# QSFP.net
KiCad netlist of a schematic drawn in Altium Designer
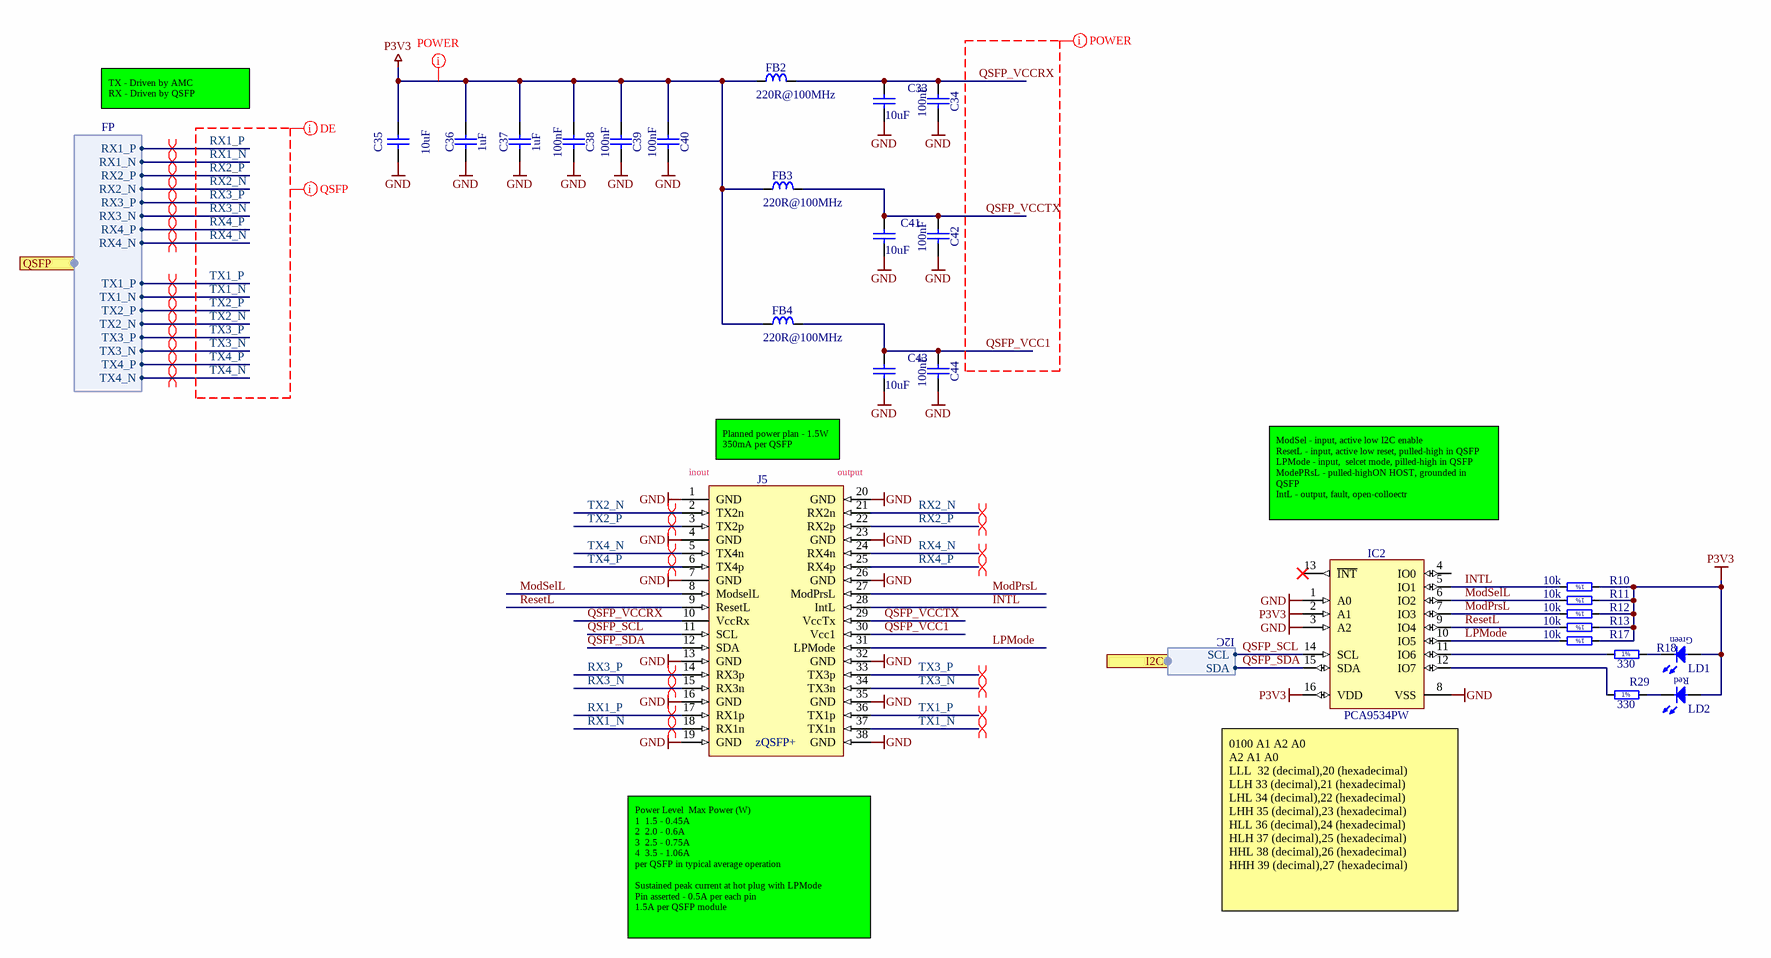
[diagram p0: QSFP.SchDoc]

(export (version "E")
  (design (tool "Eeschema 10.0.6"))
  (components
    (comp (ref "C33")
      (value "10uF")
      (footprint "CAPC2012X135N")
      (description "Non-polarised capacitor")
      (fields
        (field (name "PART NUMBER") "CC0805_10UF_10V_10%_X7R")
        (field (name "VOLTAGE") "10V")
        (field (name "AUTHOR") "CERN DEM JLC")
      )
      (libsource (lib "Capacitors") (part "Capacitor - non polarized"))
    )
    (comp (ref "C34")
      (value "100nF")
      (footprint "CAPC0603X33N")
      (description "Non-polarised capacitor")
      (fields
        (field (name "PART NUMBER") "CC0201_100NF_6.3V_10%_X5R")
        (field (name "VOLTAGE") "6.3V")
        (field (name "AUTHOR") "CERN DEM JLC")
      )
      (libsource (lib "Capacitors") (part "Capacitor - non polarized"))
    )
    (comp (ref "C35")
      (value "10uF")
      (footprint "CAPC2012X135N")
      (description "Non-polarised capacitor")
      (fields
        (field (name "PART NUMBER") "CC0805_10UF_10V_10%_X7R")
        (field (name "VOLTAGE") "10V")
        (field (name "AUTHOR") "CERN DEM JLC")
      )
      (libsource (lib "Capacitors") (part "Capacitor - non polarized"))
    )
    (comp (ref "C36")
      (value "1uF")
      (footprint "CAPC1608X87N")
      (description "Non-polarised capacitor")
      (fields
        (field (name "PART NUMBER") "CC0603_1UF_25V_10%_X7R")
        (field (name "VOLTAGE") "25V")
        (field (name "AUTHOR") "CERN DEM JLC")
      )
      (libsource (lib "Capacitors") (part "Capacitor - non polarized"))
    )
    (comp (ref "C37")
      (value "1uF")
      (footprint "CAPC1608X87N")
      (description "Non-polarised capacitor")
      (fields
        (field (name "PART NUMBER") "CC0603_1UF_25V_10%_X7R")
        (field (name "VOLTAGE") "25V")
        (field (name "AUTHOR") "CERN DEM JLC")
      )
      (libsource (lib "Capacitors") (part "Capacitor - non polarized"))
    )
    (comp (ref "C38")
      (value "100nF")
      (footprint "CAPC0603X33N")
      (description "Non-polarised capacitor")
      (fields
        (field (name "PART NUMBER") "CC0201_100NF_6.3V_10%_X5R")
        (field (name "VOLTAGE") "6.3V")
        (field (name "AUTHOR") "CERN DEM JLC")
      )
      (libsource (lib "Capacitors") (part "Capacitor - non polarized"))
    )
    (comp (ref "C39")
      (value "100nF")
      (footprint "CAPC0603X33N")
      (description "Non-polarised capacitor")
      (fields
        (field (name "PART NUMBER") "CC0201_100NF_6.3V_10%_X5R")
        (field (name "VOLTAGE") "6.3V")
        (field (name "AUTHOR") "CERN DEM JLC")
      )
      (libsource (lib "Capacitors") (part "Capacitor - non polarized"))
    )
    (comp (ref "C40")
      (value "100nF")
      (footprint "CAPC0603X33N")
      (description "Non-polarised capacitor")
      (fields
        (field (name "PART NUMBER") "CC0201_100NF_6.3V_10%_X5R")
        (field (name "VOLTAGE") "6.3V")
        (field (name "AUTHOR") "CERN DEM JLC")
      )
      (libsource (lib "Capacitors") (part "Capacitor - non polarized"))
    )
    (comp (ref "C41")
      (value "10uF")
      (footprint "CAPC2012X135N")
      (description "Non-polarised capacitor")
      (fields
        (field (name "PART NUMBER") "CC0805_10UF_10V_10%_X7R")
        (field (name "VOLTAGE") "10V")
        (field (name "AUTHOR") "CERN DEM JLC")
      )
      (libsource (lib "Capacitors") (part "Capacitor - non polarized"))
    )
    (comp (ref "C42")
      (value "100nF")
      (footprint "CAPC0603X33N")
      (description "Non-polarised capacitor")
      (fields
        (field (name "PART NUMBER") "CC0201_100NF_6.3V_10%_X5R")
        (field (name "VOLTAGE") "6.3V")
        (field (name "AUTHOR") "CERN DEM JLC")
      )
      (libsource (lib "Capacitors") (part "Capacitor - non polarized"))
    )
    (comp (ref "C43")
      (value "10uF")
      (footprint "CAPC2012X135N")
      (description "Non-polarised capacitor")
      (fields
        (field (name "PART NUMBER") "CC0805_10UF_10V_10%_X7R")
        (field (name "VOLTAGE") "10V")
        (field (name "AUTHOR") "CERN DEM JLC")
      )
      (libsource (lib "Capacitors") (part "Capacitor - non polarized"))
    )
    (comp (ref "C44")
      (value "100nF")
      (footprint "CAPC0603X33N")
      (description "Non-polarised capacitor")
      (fields
        (field (name "PART NUMBER") "CC0201_100NF_6.3V_10%_X5R")
        (field (name "VOLTAGE") "6.3V")
        (field (name "AUTHOR") "CERN DEM JLC")
      )
      (libsource (lib "Capacitors") (part "Capacitor - non polarized"))
    )
    (comp (ref "FB2")
      (value "220R@100MHz")
      (footprint "INDC2012X105N")
      (description "Inductor")
      (fields
        (field (name "PART NUMBER") "IND0805_MURATA_BLM21PG221SN1D")
        (field (name "POWER") "2A")
        (field (name "AUTHOR") "CERN DEM JLC")
      )
      (libsource (lib "Inductors & Transformers") (part "Inductor"))
    )
    (comp (ref "FB3")
      (value "220R@100MHz")
      (footprint "INDC2012X105N")
      (description "Inductor")
      (fields
        (field (name "PART NUMBER") "IND0805_MURATA_BLM21PG221SN1D")
        (field (name "POWER") "2A")
        (field (name "AUTHOR") "CERN DEM JLC")
      )
      (libsource (lib "Inductors & Transformers") (part "Inductor"))
    )
    (comp (ref "FB4")
      (value "220R@100MHz")
      (footprint "INDC2012X105N")
      (description "Inductor")
      (fields
        (field (name "PART NUMBER") "IND0805_MURATA_BLM21PG221SN1D")
        (field (name "POWER") "2A")
        (field (name "AUTHOR") "CERN DEM JLC")
      )
      (libsource (lib "Inductors & Transformers") (part "Inductor"))
    )
    (comp (ref "IC2")
      (value "PCA9534PW")
      (footprint "SOP65P640X110-16N")
      (description "8-Bit I2C-Bus and SMBus Low Power I/O Port with Interrupt")
      (fields (field (name "MANUFACTURER") "ANALOG DEVICES") (field (name "AUTHOR") "CERN DEM JLC"))
      (libsource (lib "ICs And Semiconductors") (part "PCA9534PW"))
    )
    (comp (ref "J5")
      (value "zQSFP+")
      (footprint "TYCO_1551920-2")
      (description "38Position QSFP Connector  (Quad Small Form-factor Pluggable)")
      (fields
        (field (name "PART NUMBER") "TYCO_1551920-2")
        (field (name "MANUFACTURER") "TYCO ELECTRONICS")
        (field (name "AUTHOR") "CERN DEM JLC")
      )
      (libsource (lib "Connectors") (part "QSFP+x1"))
    )
    (comp (ref "LD1")
      (value "LED_AVAGO_HSME-C120")
      (footprint "LED_AVAGO_HSME-C120")
      (description "LED Green 1C 2A")
      (fields
        (field (name "MANUFACTURER") "AVAGO TECHNOLOGIES")
        (field (name "MANUFACTURER PART NUMBER") "HSME-C120")
        (field (name "AUTHOR") "CERN DEM JMW")
      )
      (libsource (lib "ICs And Semiconductors") (part "LED Green 1C 2A"))
    )
    (comp (ref "LD2")
      (value "Red")
      (footprint "LED_AVAGO_HSME-C120rev")
      (description "LED Red Avago C120")
      (fields
        (field (name "PART NUMBER") "LED_AVAGO_HSMC-C120")
        (field (name "MANUFACTURER") "AVAGO TECHNOLOGIES")
        (field (name "AUTHOR") "CERN DEM JMW")
      )
      (libsource (lib "LIBRARY_SCH") (part "LED_SMD_90deg_mini_R"))
    )
    (comp (ref "R10")
      (value "10k")
      (footprint "RESC1005X40N")
      (description "Resistor - 1%")
      (fields
        (field (name "PART NUMBER") "R0402_10K_1%_0.0625W_100PPM")
        (field (name "POWER") "0.0625W")
        (field (name "AUTHOR") "CERN DEM JLC")
      )
      (libsource (lib "Resistors") (part "Resistor - 1%"))
    )
    (comp (ref "R11")
      (value "10k")
      (footprint "RESC1005X40N")
      (description "Resistor - 1%")
      (fields
        (field (name "PART NUMBER") "R0402_10K_1%_0.0625W_100PPM")
        (field (name "POWER") "0.0625W")
        (field (name "AUTHOR") "CERN DEM JLC")
      )
      (libsource (lib "Resistors") (part "Resistor - 1%"))
    )
    (comp (ref "R12")
      (value "10k")
      (footprint "RESC1005X40N")
      (description "Resistor - 1%")
      (fields
        (field (name "PART NUMBER") "R0402_10K_1%_0.0625W_100PPM")
        (field (name "POWER") "0.0625W")
        (field (name "AUTHOR") "CERN DEM JLC")
      )
      (libsource (lib "Resistors") (part "Resistor - 1%"))
    )
    (comp (ref "R13")
      (value "10k")
      (footprint "RESC1005X40N")
      (description "Resistor - 1%")
      (fields
        (field (name "PART NUMBER") "R0402_10K_1%_0.0625W_100PPM")
        (field (name "POWER") "0.0625W")
        (field (name "AUTHOR") "CERN DEM JLC")
      )
      (libsource (lib "Resistors") (part "Resistor - 1%"))
    )
    (comp (ref "R17")
      (value "10k")
      (footprint "RESC1005X40N")
      (description "Resistor - 1%")
      (fields
        (field (name "PART NUMBER") "R0402_10K_1%_0.0625W_100PPM")
        (field (name "POWER") "0.0625W")
        (field (name "AUTHOR") "CERN DEM JLC")
      )
      (libsource (lib "Resistors") (part "Resistor - 1%"))
    )
    (comp (ref "R18")
      (value "330")
      (footprint "RESC1608X55N")
      (description "Resistor - 1%")
      (fields
        (field (name "PART NUMBER") "R0603_330R_1%_0.1W_100PPM")
        (field (name "POWER") "0.1W")
        (field (name "AUTHOR") "CERN DEM JLC")
      )
      (libsource (lib "Resistors") (part "Resistor - 1%"))
    )
    (comp (ref "R29")
      (value "330")
      (footprint "RESC1608X55N")
      (description "Resistor - 1%")
      (fields
        (field (name "PART NUMBER") "R0603_330R_1%_0.1W_100PPM")
        (field (name "POWER") "0.1W")
        (field (name "AUTHOR") "CERN DEM JLC")
      )
      (libsource (lib "Resistors") (part "Resistor - 1%"))
    )
  )
  (nets
    (net (code "3") (name "/INTL") (class "Default")
      (node (ref "IC2") (pin "5") (pinfunction "IO1_5") (pintype "bidirectional"))
      (node (ref "J5") (pin "28") (pinfunction "IntL_28") (pintype "input"))
      (node (ref "R10") (pin "2") (pinfunction "2_2") (pintype "passive"))
    )
    (net (code "4") (name "/LPMode") (class "Default")
      (node (ref "IC2") (pin "10") (pinfunction "IO5_10") (pintype "bidirectional"))
      (node (ref "J5") (pin "31") (pinfunction "LPMode_31") (pintype "input"))
      (node (ref "R17") (pin "2") (pinfunction "2_2") (pintype "passive"))
    )
    (net (code "5") (name "/ModPrsL") (class "Default")
      (node (ref "IC2") (pin "7") (pinfunction "IO3_7") (pintype "bidirectional"))
      (node (ref "J5") (pin "27") (pinfunction "ModPrsL_27") (pintype "input"))
      (node (ref "R12") (pin "2") (pinfunction "2_2") (pintype "passive"))
    )
    (net (code "6") (name "/ModSelL") (class "Default")
      (node (ref "IC2") (pin "6") (pinfunction "IO2_6") (pintype "bidirectional"))
      (node (ref "J5") (pin "8") (pinfunction "ModselL_8") (pintype "input"))
      (node (ref "R11") (pin "2") (pinfunction "2_2") (pintype "passive"))
    )
    (net (code "7") (name "/QSFP_SCL") (class "Default")
      (node (ref "IC2") (pin "14") (pinfunction "SCL_14") (pintype "input"))
      (node (ref "J5") (pin "11") (pinfunction "SCL_11") (pintype "input"))
    )
    (net (code "8") (name "/QSFP_SDA") (class "Default")
      (node (ref "IC2") (pin "15") (pinfunction "SDA_15") (pintype "bidirectional"))
      (node (ref "J5") (pin "12") (pinfunction "SDA_12") (pintype "input"))
    )
    (net (code "9") (name "/QSFP_VCC1") (class "Default")
      (node (ref "C43") (pin "1") (pinfunction "1_1") (pintype "passive"))
      (node (ref "C44") (pin "1") (pinfunction "1_1") (pintype "passive"))
      (node (ref "FB4") (pin "2") (pinfunction "2_2") (pintype "passive"))
      (node (ref "J5") (pin "30") (pinfunction "Vcc1_30") (pintype "input"))
    )
    (net (code "10") (name "/QSFP_VCCRX") (class "Default")
      (node (ref "C33") (pin "1") (pinfunction "1_1") (pintype "passive"))
      (node (ref "C34") (pin "1") (pinfunction "1_1") (pintype "passive"))
      (node (ref "FB2") (pin "2") (pinfunction "2_2") (pintype "passive"))
      (node (ref "J5") (pin "10") (pinfunction "VccRx_10") (pintype "power_in"))
    )
    (net (code "11") (name "/QSFP_VCCTX") (class "Default")
      (node (ref "C41") (pin "1") (pinfunction "1_1") (pintype "passive"))
      (node (ref "C42") (pin "1") (pinfunction "1_1") (pintype "passive"))
      (node (ref "FB3") (pin "2") (pinfunction "2_2") (pintype "passive"))
      (node (ref "J5") (pin "29") (pinfunction "VccTx_29") (pintype "input"))
    )
    (net (code "12") (name "/RX1_N") (class "Default")
      (node (ref "J5") (pin "18") (pinfunction "RX1n_18") (pintype "input"))
    )
    (net (code "13") (name "/RX1_P") (class "Default")
      (node (ref "J5") (pin "17") (pinfunction "RX1p_17") (pintype "input"))
    )
    (net (code "14") (name "/RX2_N") (class "Default")
      (node (ref "J5") (pin "21") (pinfunction "RX2n_21") (pintype "input"))
    )
    (net (code "15") (name "/RX2_P") (class "Default")
      (node (ref "J5") (pin "22") (pinfunction "RX2p_22") (pintype "input"))
    )
    (net (code "16") (name "/RX3_N") (class "Default")
      (node (ref "J5") (pin "15") (pinfunction "RX3n_15") (pintype "input"))
    )
    (net (code "17") (name "/RX3_P") (class "Default")
      (node (ref "J5") (pin "14") (pinfunction "RX3p_14") (pintype "input"))
    )
    (net (code "18") (name "/RX4_N") (class "Default")
      (node (ref "J5") (pin "24") (pinfunction "RX4n_24") (pintype "input"))
    )
    (net (code "19") (name "/RX4_P") (class "Default")
      (node (ref "J5") (pin "25") (pinfunction "RX4p_25") (pintype "input"))
    )
    (net (code "20") (name "/ResetL") (class "Default")
      (node (ref "IC2") (pin "9") (pinfunction "IO4_9") (pintype "bidirectional"))
      (node (ref "J5") (pin "9") (pinfunction "ResetL_9") (pintype "input"))
      (node (ref "R13") (pin "2") (pinfunction "2_2") (pintype "passive"))
    )
    (net (code "21") (name "/TX1_N") (class "Default")
      (node (ref "J5") (pin "37") (pinfunction "TX1n_37") (pintype "input"))
    )
    (net (code "22") (name "/TX1_P") (class "Default")
      (node (ref "J5") (pin "36") (pinfunction "TX1p_36") (pintype "input"))
    )
    (net (code "23") (name "/TX2_N") (class "Default")
      (node (ref "J5") (pin "2") (pinfunction "TX2n_2") (pintype "input"))
    )
    (net (code "24") (name "/TX2_P") (class "Default")
      (node (ref "J5") (pin "3") (pinfunction "TX2p_3") (pintype "input"))
    )
    (net (code "25") (name "/TX3_N") (class "Default")
      (node (ref "J5") (pin "34") (pinfunction "TX3n_34") (pintype "input"))
    )
    (net (code "26") (name "/TX3_P") (class "Default")
      (node (ref "J5") (pin "33") (pinfunction "TX3p_33") (pintype "input"))
    )
    (net (code "27") (name "/TX4_N") (class "Default")
      (node (ref "J5") (pin "5") (pinfunction "TX4n_5") (pintype "input"))
    )
    (net (code "28") (name "/TX4_P") (class "Default")
      (node (ref "J5") (pin "6") (pinfunction "TX4p_6") (pintype "input"))
    )
    (net (code "31") (name "GND") (class "Default")
      (node (ref "C33") (pin "2") (pinfunction "2_2") (pintype "passive"))
      (node (ref "C34") (pin "2") (pinfunction "2_2") (pintype "passive"))
      (node (ref "C35") (pin "2") (pinfunction "2_2") (pintype "passive"))
      (node (ref "C36") (pin "1") (pinfunction "1_1") (pintype "passive"))
      (node (ref "C37") (pin "1") (pinfunction "1_1") (pintype "passive"))
      (node (ref "C38") (pin "2") (pinfunction "2_2") (pintype "passive"))
      (node (ref "C39") (pin "2") (pinfunction "2_2") (pintype "passive"))
      (node (ref "C40") (pin "2") (pinfunction "2_2") (pintype "passive"))
      (node (ref "C41") (pin "2") (pinfunction "2_2") (pintype "passive"))
      (node (ref "C42") (pin "2") (pinfunction "2_2") (pintype "passive"))
      (node (ref "C43") (pin "2") (pinfunction "2_2") (pintype "passive"))
      (node (ref "C44") (pin "2") (pinfunction "2_2") (pintype "passive"))
      (node (ref "IC2") (pin "1") (pinfunction "A0_1") (pintype "input"))
      (node (ref "IC2") (pin "3") (pinfunction "A2_3") (pintype "input"))
      (node (ref "IC2") (pin "8") (pinfunction "VSS_8") (pintype "power_in"))
      (node (ref "J5") (pin "1") (pinfunction "GND_1") (pintype "power_in"))
      (node (ref "J5") (pin "13") (pinfunction "GND_13") (pintype "input"))
      (node (ref "J5") (pin "16") (pinfunction "GND_16") (pintype "input"))
      (node (ref "J5") (pin "19") (pinfunction "GND_19") (pintype "input"))
      (node (ref "J5") (pin "20") (pinfunction "GND_20") (pintype "input"))
      (node (ref "J5") (pin "23") (pinfunction "GND_23") (pintype "input"))
      (node (ref "J5") (pin "26") (pinfunction "GND_26") (pintype "input"))
      (node (ref "J5") (pin "32") (pinfunction "GND_32") (pintype "input"))
      (node (ref "J5") (pin "35") (pinfunction "GND_35") (pintype "input"))
      (node (ref "J5") (pin "38") (pinfunction "GND_38") (pintype "input"))
      (node (ref "J5") (pin "4") (pinfunction "GND_4") (pintype "power_in"))
      (node (ref "J5") (pin "7") (pinfunction "GND_7") (pintype "power_in"))
    )
    (net (code "32") (name "Net-(IC2-IO6)") (class "Default")
      (node (ref "IC2") (pin "11") (pinfunction "IO6_11") (pintype "bidirectional"))
      (node (ref "R18") (pin "1") (pinfunction "1_1") (pintype "passive"))
    )
    (net (code "33") (name "Net-(IC2-IO7)") (class "Default")
      (node (ref "IC2") (pin "12") (pinfunction "IO7_12") (pintype "bidirectional"))
      (node (ref "R29") (pin "1") (pinfunction "1_1") (pintype "passive"))
    )
    (net (code "34") (name "Net-(LD1-C)") (class "Default")
      (node (ref "LD1") (pin "1") (pinfunction "C_1") (pintype "passive"))
      (node (ref "R18") (pin "2") (pinfunction "2_2") (pintype "passive"))
    )
    (net (code "35") (name "Net-(LD2-C)") (class "Default")
      (node (ref "LD2") (pin "2") (pinfunction "C_2") (pintype "passive"))
      (node (ref "R29") (pin "2") (pinfunction "2_2") (pintype "passive"))
    )
    (net (code "36") (name "P3V3") (class "Default")
      (node (ref "C35") (pin "1") (pinfunction "1_1") (pintype "passive"))
      (node (ref "C36") (pin "2") (pinfunction "2_2") (pintype "passive"))
      (node (ref "C37") (pin "2") (pinfunction "2_2") (pintype "passive"))
      (node (ref "C38") (pin "1") (pinfunction "1_1") (pintype "passive"))
      (node (ref "C39") (pin "1") (pinfunction "1_1") (pintype "passive"))
      (node (ref "C40") (pin "1") (pinfunction "1_1") (pintype "passive"))
      (node (ref "FB2") (pin "1") (pinfunction "1_1") (pintype "passive"))
      (node (ref "FB3") (pin "1") (pinfunction "1_1") (pintype "passive"))
      (node (ref "FB4") (pin "1") (pinfunction "1_1") (pintype "passive"))
      (node (ref "IC2") (pin "16") (pinfunction "VDD_16") (pintype "bidirectional"))
      (node (ref "IC2") (pin "2") (pinfunction "A1_2") (pintype "input"))
      (node (ref "LD1") (pin "2") (pinfunction "A_2") (pintype "passive"))
      (node (ref "LD2") (pin "1") (pinfunction "A_1") (pintype "passive"))
      (node (ref "R10") (pin "1") (pinfunction "1_1") (pintype "passive"))
      (node (ref "R11") (pin "1") (pinfunction "1_1") (pintype "passive"))
      (node (ref "R12") (pin "1") (pinfunction "1_1") (pintype "passive"))
      (node (ref "R13") (pin "1") (pinfunction "1_1") (pintype "passive"))
      (node (ref "R17") (pin "1") (pinfunction "1_1") (pintype "passive"))
    )
    (net (code "37") (name "unconnected-(IC2-IO0-Pad4)") (class "Default")
      (node (ref "IC2") (pin "4") (pinfunction "IO0_4") (pintype "bidirectional"))
    )
    (net (code "38") (name "unconnected-(IC2-~{INT}-Pad13)") (class "Default")
      (node (ref "IC2") (pin "13") (pinfunction "~{INT}_13") (pintype "output+no_connect"))
    )
  )
)
